# Duang60v2.net
KiCad netlist of a schematic drawn in Altium Designer
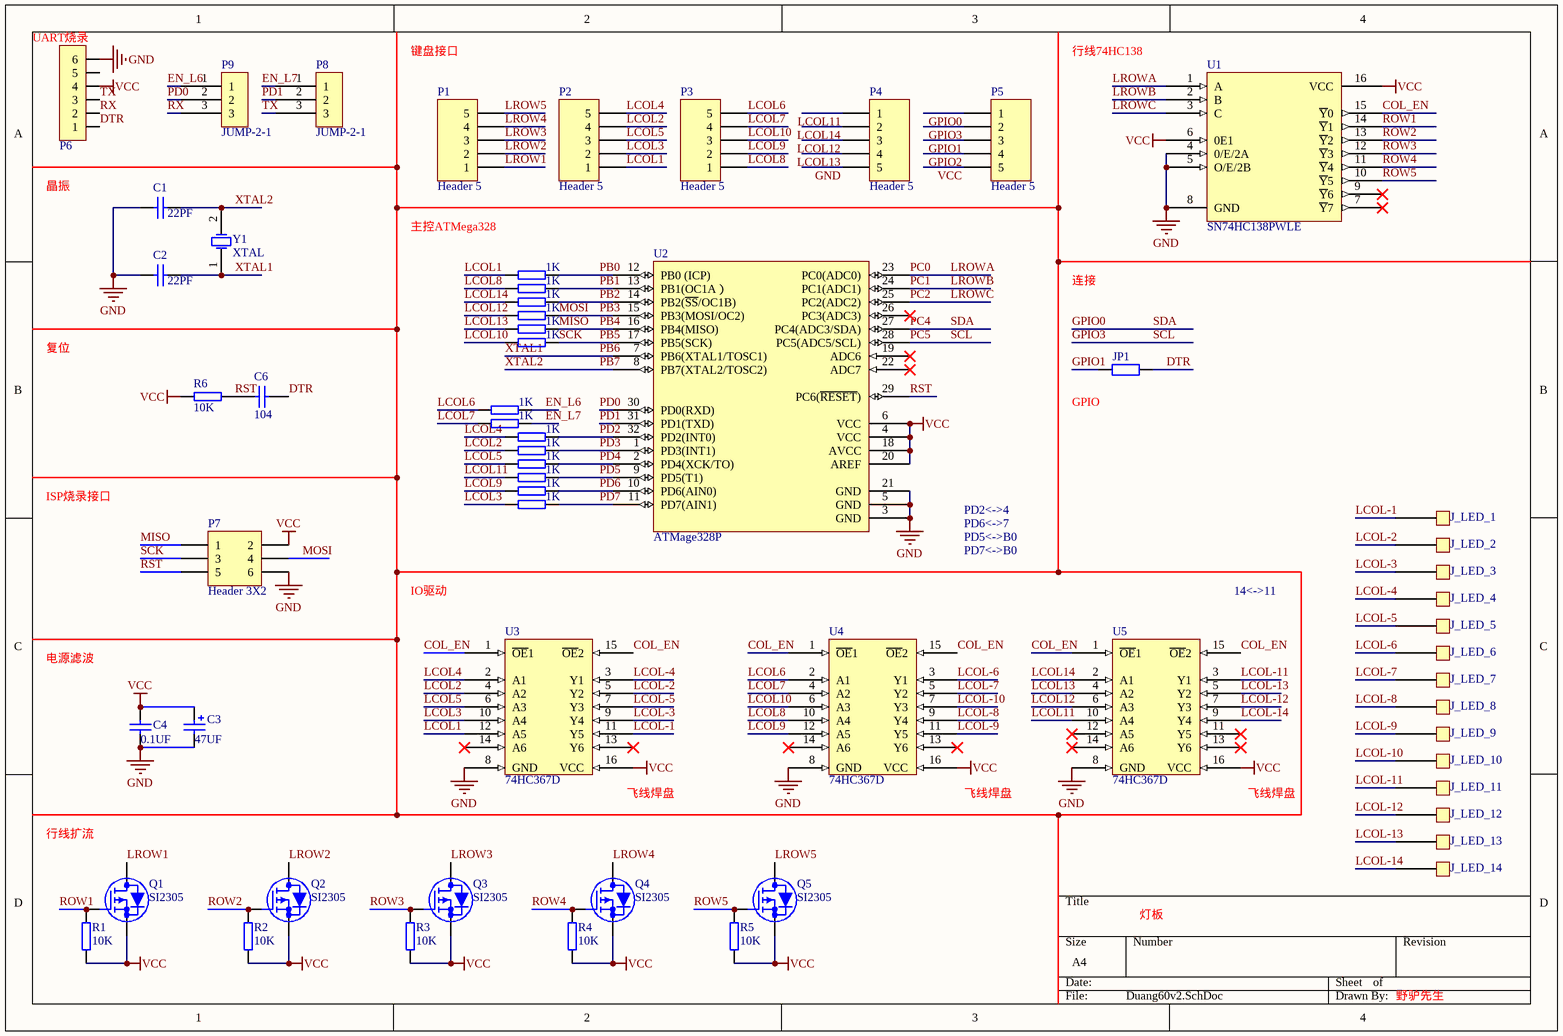
[diagram p0: Duang60v2.SchDoc]

(export (version "E")
  (design (tool "Eeschema 10.0.6"))
  (components
    (comp (ref "C1")
      (value "22PF")
      (footprint "c0805")
      (description "Capacitor (Semiconductor SIM Model)")
      (fields (field (name "Comment") "Cap Semi") (field (name "PUBLISHER") "Altium Limited"))
      (libsource (lib "Miscellaneous Devices") (part "Cap Semi"))
    )
    (comp (ref "C2")
      (value "22PF")
      (footprint "c0805")
      (description "Capacitor (Semiconductor SIM Model)")
      (fields (field (name "Comment") "Cap Semi") (field (name "PUBLISHER") "Altium Limited"))
      (libsource (lib "Miscellaneous Devices") (part "Cap Semi"))
    )
    (comp (ref "C3")
      (value "47UF")
      (footprint "CAPT3216")
      (description "Polarized Capacitor (Axial)")
      (fields (field (name "Comment") "Cap Pol2") (field (name "PUBLISHER") "Altium Limited"))
      (libsource (lib "Miscellaneous Devices") (part "Cap Pol2"))
    )
    (comp (ref "C4")
      (value "0.1UF")
      (footprint "c0805")
      (description "Capacitor (Semiconductor SIM Model)")
      (fields (field (name "Comment") "Cap Semi") (field (name "PUBLISHER") "Altium Limited"))
      (libsource (lib "Miscellaneous Devices") (part "Cap Semi"))
    )
    (comp (ref "C6")
      (value "104")
      (footprint "c0805")
      (description "Chip Capacitor, Silkscreen Border")
      (fields
        (field (name "VOLTAGE") "63V")
        (field (name "TOLERANCE") "Y5V")
        (field (name "PUBLISHER") "Altium Limited")
      )
      (libsource (lib "Miscellaneous Integrated Library") (part "Cap Chip 2"))
    )
    (comp (ref "JP1")
      (value "0")
      (footprint "c0805")
      (description "Resistor")
      (libsource (lib "SCH_Passive") (part "Res_0805"))
    )
    (comp (ref "J_LED_1") (value "JUMP1") (footprint "焊盘") (libsource (lib "SCH_Other") (part "JUMP1")))
    (comp (ref "J_LED_2") (value "JUMP1") (footprint "焊盘") (libsource (lib "SCH_Other") (part "JUMP1")))
    (comp (ref "J_LED_3") (value "JUMP1") (footprint "焊盘") (libsource (lib "SCH_Other") (part "JUMP1")))
    (comp (ref "J_LED_4") (value "JUMP1") (footprint "焊盘") (libsource (lib "SCH_Other") (part "JUMP1")))
    (comp (ref "J_LED_5") (value "JUMP1") (footprint "焊盘") (libsource (lib "SCH_Other") (part "JUMP1")))
    (comp (ref "J_LED_6") (value "JUMP1") (footprint "焊盘") (libsource (lib "SCH_Other") (part "JUMP1")))
    (comp (ref "J_LED_7") (value "JUMP1") (footprint "焊盘") (libsource (lib "SCH_Other") (part "JUMP1")))
    (comp (ref "J_LED_8") (value "JUMP1") (footprint "焊盘") (libsource (lib "SCH_Other") (part "JUMP1")))
    (comp (ref "J_LED_9") (value "JUMP1") (footprint "焊盘") (libsource (lib "SCH_Other") (part "JUMP1")))
    (comp (ref "J_LED_10") (value "JUMP1") (footprint "焊盘") (libsource (lib "SCH_Other") (part "JUMP1")))
    (comp (ref "J_LED_11") (value "JUMP1") (footprint "焊盘") (libsource (lib "SCH_Other") (part "JUMP1")))
    (comp (ref "J_LED_12") (value "JUMP1") (footprint "焊盘") (libsource (lib "SCH_Other") (part "JUMP1")))
    (comp (ref "J_LED_13") (value "JUMP1") (footprint "焊盘") (libsource (lib "SCH_Other") (part "JUMP1")))
    (comp (ref "J_LED_14") (value "JUMP1") (footprint "焊盘") (libsource (lib "SCH_Other") (part "JUMP1")))
    (comp (ref "P1")
      (value "Header 5")
      (footprint "HDR1X5")
      (description "Header, 5-Pin")
      (fields (field (name "PUBLISHER") "Altium Limited"))
      (libsource (lib "Miscellaneous Connectors") (part "Header 5"))
    )
    (comp (ref "P2")
      (value "Header 5")
      (footprint "HDR1X5")
      (description "Header, 5-Pin")
      (fields (field (name "PUBLISHER") "Altium Limited"))
      (libsource (lib "Miscellaneous Connectors") (part "Header 5"))
    )
    (comp (ref "P3")
      (value "Header 5")
      (footprint "HDR1X5")
      (description "Header, 5-Pin")
      (fields (field (name "PUBLISHER") "Altium Limited"))
      (libsource (lib "Miscellaneous Connectors") (part "Header 5"))
    )
    (comp (ref "P4")
      (value "Header 5")
      (footprint "HDR1X5")
      (description "Header, 5-Pin")
      (fields (field (name "PUBLISHER") "Altium Limited"))
      (libsource (lib "") (part "Header 5_1"))
    )
    (comp (ref "P5")
      (value "Header 5")
      (footprint "HDR1X5")
      (description "Header, 5-Pin")
      (fields (field (name "PUBLISHER") "Altium Limited"))
      (libsource (lib "") (part "Header 5_1"))
    )
    (comp (ref "P6")
      (value "HDR1X6_180_2.54")
      (footprint "PCB_Connector:HDR1X6_180_2.54")
      (description "Header")
      (libsource (lib "SCH_Connector") (part "HDR1X6_180_2.54"))
    )
    (comp (ref "P7")
      (value "Header 3X2")
      (footprint "HDR2X3")
      (description "Header, 3-Pin, Dual row")
      (fields (field (name "PUBLISHER") "Altium Limited"))
      (libsource (lib "Miscellaneous Connectors") (part "Header 3X2"))
    )
    (comp (ref "P8")
      (value "JUMP-2-1")
      (footprint "JUMP-2-1")
      (libsource (lib "SCH_Other") (part "JUMP-2-1"))
    )
    (comp (ref "P9")
      (value "JUMP-2-1")
      (footprint "JUMP-2-1")
      (libsource (lib "SCH_Other") (part "JUMP-2-1"))
    )
    (comp (ref "Q1")
      (value "SI2305")
      (footprint "si2312")
      (description "P-Channel MOSFET")
      (fields (field (name "PARTNUMBER") "SI2305") (field (name "PUBLISHER") "Altium Limited"))
      (libsource (lib "Miscellaneous Integrated Library") (part "MOSFET-P"))
    )
    (comp (ref "Q2")
      (value "SI2305")
      (footprint "si2312")
      (description "P-Channel MOSFET")
      (fields (field (name "PARTNUMBER") "SI2305") (field (name "PUBLISHER") "Altium Limited"))
      (libsource (lib "Miscellaneous Integrated Library") (part "MOSFET-P"))
    )
    (comp (ref "Q3")
      (value "SI2305")
      (footprint "si2312")
      (description "P-Channel MOSFET")
      (fields (field (name "PARTNUMBER") "SI2305") (field (name "PUBLISHER") "Altium Limited"))
      (libsource (lib "Miscellaneous Integrated Library") (part "MOSFET-P"))
    )
    (comp (ref "Q4")
      (value "SI2305")
      (footprint "si2312")
      (description "P-Channel MOSFET")
      (fields (field (name "PARTNUMBER") "SI2305") (field (name "PUBLISHER") "Altium Limited"))
      (libsource (lib "Miscellaneous Integrated Library") (part "MOSFET-P"))
    )
    (comp (ref "Q5")
      (value "SI2305")
      (footprint "si2312")
      (description "P-Channel MOSFET")
      (fields (field (name "PARTNUMBER") "SI2305") (field (name "PUBLISHER") "Altium Limited"))
      (libsource (lib "Miscellaneous Integrated Library") (part "MOSFET-P"))
    )
    (comp (ref "R1")
      (value "10K")
      (footprint "r0806")
      (description "Chip Resistor, Border Silkscreen On PCB Library")
      (fields (field (name "TOLERANCE") "5%") (field (name "PUBLISHER") "Altium Limited"))
      (libsource (lib "Miscellaneous Integrated Library") (part "Res Chip 2p 2"))
    )
    (comp (ref "R2")
      (value "10K")
      (footprint "r0806")
      (description "Chip Resistor, Border Silkscreen On PCB Library")
      (fields (field (name "TOLERANCE") "5%") (field (name "PUBLISHER") "Altium Limited"))
      (libsource (lib "Miscellaneous Integrated Library") (part "Res Chip 2p 2"))
    )
    (comp (ref "R3")
      (value "10K")
      (footprint "r0806")
      (description "Chip Resistor, Border Silkscreen On PCB Library")
      (fields (field (name "TOLERANCE") "5%") (field (name "PUBLISHER") "Altium Limited"))
      (libsource (lib "Miscellaneous Integrated Library") (part "Res Chip 2p 2"))
    )
    (comp (ref "R4")
      (value "10K")
      (footprint "r0806")
      (description "Chip Resistor, Border Silkscreen On PCB Library")
      (fields (field (name "TOLERANCE") "5%") (field (name "PUBLISHER") "Altium Limited"))
      (libsource (lib "Miscellaneous Integrated Library") (part "Res Chip 2p 2"))
    )
    (comp (ref "R5")
      (value "10K")
      (footprint "r0806")
      (description "Chip Resistor, Border Silkscreen On PCB Library")
      (fields (field (name "TOLERANCE") "5%") (field (name "PUBLISHER") "Altium Limited"))
      (libsource (lib "Miscellaneous Integrated Library") (part "Res Chip 2p 2"))
    )
    (comp (ref "R6")
      (value "10K")
      (footprint "r0806")
      (description "Chip Resistor, Border Silkscreen On PCB Library")
      (fields (field (name "TOLERANCE") "5%") (field (name "PUBLISHER") "Altium Limited"))
      (libsource (lib "Miscellaneous Integrated Library") (part "Res Chip 2p 2"))
    )
    (comp (ref "R7")
      (value "1K")
      (footprint "JP")
      (description "Chip Resistor, Border Silkscreen On PCB Library")
      (fields
        (field (name "TOLERANCE") "5%")
        (field (name "Comment") "1k")
        (field (name "PUBLISHER") "Altium Limited")
      )
      (libsource (lib "Miscellaneous Integrated Library") (part "Res Chip 2p 2"))
    )
    (comp (ref "R8")
      (value "1K")
      (footprint "JP")
      (description "Chip Resistor, Border Silkscreen On PCB Library")
      (fields
        (field (name "TOLERANCE") "5%")
        (field (name "Comment") "1k")
        (field (name "PUBLISHER") "Altium Limited")
      )
      (libsource (lib "Miscellaneous Integrated Library") (part "Res Chip 2p 2"))
    )
    (comp (ref "R9")
      (value "1K")
      (footprint "JP")
      (description "Chip Resistor, Border Silkscreen On PCB Library")
      (fields
        (field (name "TOLERANCE") "5%")
        (field (name "Comment") "1k")
        (field (name "PUBLISHER") "Altium Limited")
      )
      (libsource (lib "Miscellaneous Integrated Library") (part "Res Chip 2p 2"))
    )
    (comp (ref "R10")
      (value "1K")
      (footprint "JP")
      (description "Chip Resistor, Border Silkscreen On PCB Library")
      (fields
        (field (name "TOLERANCE") "5%")
        (field (name "Comment") "1k")
        (field (name "PUBLISHER") "Altium Limited")
      )
      (libsource (lib "Miscellaneous Integrated Library") (part "Res Chip 2p 2"))
    )
    (comp (ref "R11")
      (value "1K")
      (footprint "JP")
      (description "Chip Resistor, Border Silkscreen On PCB Library")
      (fields
        (field (name "TOLERANCE") "5%")
        (field (name "Comment") "1k")
        (field (name "PUBLISHER") "Altium Limited")
      )
      (libsource (lib "Miscellaneous Integrated Library") (part "Res Chip 2p 2"))
    )
    (comp (ref "R12")
      (value "1K")
      (footprint "JP")
      (description "Chip Resistor, Border Silkscreen On PCB Library")
      (fields
        (field (name "TOLERANCE") "5%")
        (field (name "Comment") "1k")
        (field (name "PUBLISHER") "Altium Limited")
      )
      (libsource (lib "Miscellaneous Integrated Library") (part "Res Chip 2p 2"))
    )
    (comp (ref "R13")
      (value "1K")
      (footprint "JP")
      (description "Chip Resistor, Border Silkscreen On PCB Library")
      (fields
        (field (name "TOLERANCE") "5%")
        (field (name "Comment") "1k")
        (field (name "PUBLISHER") "Altium Limited")
      )
      (libsource (lib "Miscellaneous Integrated Library") (part "Res Chip 2p 2"))
    )
    (comp (ref "R14")
      (value "1K")
      (footprint "JP")
      (description "Chip Resistor, Border Silkscreen On PCB Library")
      (fields
        (field (name "TOLERANCE") "5%")
        (field (name "Comment") "1k")
        (field (name "PUBLISHER") "Altium Limited")
      )
      (libsource (lib "Miscellaneous Integrated Library") (part "Res Chip 2p 2"))
    )
    (comp (ref "R15")
      (value "1K")
      (footprint "JP")
      (description "Chip Resistor, Border Silkscreen On PCB Library")
      (fields
        (field (name "TOLERANCE") "5%")
        (field (name "Comment") "1k")
        (field (name "PUBLISHER") "Altium Limited")
      )
      (libsource (lib "Miscellaneous Integrated Library") (part "Res Chip 2p 2"))
    )
    (comp (ref "R16")
      (value "1K")
      (footprint "JP")
      (description "Chip Resistor, Border Silkscreen On PCB Library")
      (fields
        (field (name "TOLERANCE") "5%")
        (field (name "Comment") "1k")
        (field (name "PUBLISHER") "Altium Limited")
      )
      (libsource (lib "Miscellaneous Integrated Library") (part "Res Chip 2p 2"))
    )
    (comp (ref "R17")
      (value "1K")
      (footprint "JP")
      (description "Chip Resistor, Border Silkscreen On PCB Library")
      (fields
        (field (name "TOLERANCE") "5%")
        (field (name "Comment") "1k")
        (field (name "PUBLISHER") "Altium Limited")
      )
      (libsource (lib "Miscellaneous Integrated Library") (part "Res Chip 2p 2"))
    )
    (comp (ref "R18")
      (value "1K")
      (footprint "JP")
      (description "Chip Resistor, Border Silkscreen On PCB Library")
      (fields
        (field (name "TOLERANCE") "5%")
        (field (name "Comment") "1k")
        (field (name "PUBLISHER") "Altium Limited")
      )
      (libsource (lib "Miscellaneous Integrated Library") (part "Res Chip 2p 2"))
    )
    (comp (ref "R19")
      (value "1K")
      (footprint "JP")
      (description "Chip Resistor, Border Silkscreen On PCB Library")
      (fields
        (field (name "TOLERANCE") "5%")
        (field (name "Comment") "1k")
        (field (name "PUBLISHER") "Altium Limited")
      )
      (libsource (lib "Miscellaneous Integrated Library") (part "Res Chip 2p 2"))
    )
    (comp (ref "R20")
      (value "1K")
      (footprint "JP")
      (description "Chip Resistor, Border Silkscreen On PCB Library")
      (fields
        (field (name "TOLERANCE") "5%")
        (field (name "Comment") "1k")
        (field (name "PUBLISHER") "Altium Limited")
      )
      (libsource (lib "Miscellaneous Integrated Library") (part "Res Chip 2p 2"))
    )
    (comp (ref "U1")
      (value "SN74HC138PWLE")
      (footprint "TSSOP_16")
      (libsource (lib "野驴集成库") (part "SN74HC138PWLE"))
    )
    (comp (ref "U2") (value "ATMage328P") (footprint "TQFP_32") (libsource (lib "野驴集成库") (part "ATMage328P")))
    (comp (ref "U3") (value "74HC367D") (footprint "SOIC16") (libsource (lib "野驴集成库") (part "74HC367D")))
    (comp (ref "U4") (value "74HC367D") (footprint "SOIC16") (libsource (lib "野驴集成库") (part "74HC367D")))
    (comp (ref "U5") (value "74HC367D") (footprint "SOIC16") (libsource (lib "野驴集成库") (part "74HC367D")))
    (comp (ref "Y1")
      (value "XTAL")
      (footprint "XTAL_DIP")
      (description "Crystal Oscillator")
      (fields (field (name "PUBLISHER") "Altium Limited"))
      (libsource (lib "Miscellaneous Devices") (part "XTAL"))
    )
  )
  (nets
    (net (code "1") (name "/COL_EN") (class "Default")
      (node (ref "U1") (pin "15") (pinfunction "~{Y}0_15") (pintype "output"))
      (node (ref "U3") (pin "1") (pinfunction "~{OE}1_1") (pintype "input"))
      (node (ref "U3") (pin "15") (pinfunction "~{OE}2_15") (pintype "input"))
      (node (ref "U4") (pin "1") (pinfunction "~{OE}1_1") (pintype "input"))
      (node (ref "U4") (pin "15") (pinfunction "~{OE}2_15") (pintype "input"))
      (node (ref "U5") (pin "1") (pinfunction "~{OE}1_1") (pintype "input"))
      (node (ref "U5") (pin "15") (pinfunction "~{OE}2_15") (pintype "input"))
    )
    (net (code "2") (name "/DTR") (class "Default")
      (node (ref "C6") (pin "2") (pinfunction "2_2") (pintype "passive"))
      (node (ref "JP1") (pin "2") (pinfunction "2_2") (pintype "passive"))
      (node (ref "P6") (pin "1") (pinfunction "1_1") (pintype "passive"))
    )
    (net (code "3") (name "/EN_L6") (class "Default")
      (node (ref "P9") (pin "1") (pinfunction "1_1") (pintype "passive"))
      (node (ref "R12") (pin "2") (pinfunction "2_2") (pintype "passive"))
    )
    (net (code "4") (name "/EN_L7") (class "Default")
      (node (ref "P8") (pin "1") (pinfunction "1_1") (pintype "passive"))
      (node (ref "R13") (pin "2") (pinfunction "2_2") (pintype "passive"))
    )
    (net (code "5") (name "/GPIO0") (class "Default")
      (node (ref "P5") (pin "1") (pinfunction "1_1") (pintype "passive"))
      (node (ref "U2") (pin "27") (pinfunction "PC4(ADC3/SDA)_27") (pintype "bidirectional"))
    )
    (net (code "6") (name "/GPIO1") (class "Default")
      (node (ref "JP1") (pin "1") (pinfunction "1_1") (pintype "passive"))
      (node (ref "P5") (pin "3") (pinfunction "3_3") (pintype "passive"))
    )
    (net (code "7") (name "/GPIO2") (class "Default")
      (node (ref "P5") (pin "4") (pinfunction "4_4") (pintype "passive"))
    )
    (net (code "8") (name "/GPIO3") (class "Default")
      (node (ref "P5") (pin "2") (pinfunction "2_2") (pintype "passive"))
      (node (ref "U2") (pin "28") (pinfunction "PC5(ADC5/SCL)_28") (pintype "bidirectional"))
    )
    (net (code "9") (name "/LCOL-1") (class "Default")
      (node (ref "J_LED_1") (pin "1") (pinfunction "1_1") (pintype "passive"))
      (node (ref "U3") (pin "11") (pinfunction "Y5_11") (pintype "input"))
    )
    (net (code "10") (name "/LCOL-2") (class "Default")
      (node (ref "J_LED_2") (pin "1") (pinfunction "1_1") (pintype "passive"))
      (node (ref "U3") (pin "5") (pinfunction "Y2_5") (pintype "input"))
    )
    (net (code "11") (name "/LCOL-3") (class "Default")
      (node (ref "J_LED_3") (pin "1") (pinfunction "1_1") (pintype "passive"))
      (node (ref "U3") (pin "9") (pinfunction "Y4_9") (pintype "input"))
    )
    (net (code "12") (name "/LCOL-4") (class "Default")
      (node (ref "J_LED_4") (pin "1") (pinfunction "1_1") (pintype "passive"))
      (node (ref "U3") (pin "3") (pinfunction "Y1_3") (pintype "input"))
    )
    (net (code "13") (name "/LCOL-5") (class "Default")
      (node (ref "J_LED_5") (pin "1") (pinfunction "1_1") (pintype "passive"))
      (node (ref "U3") (pin "7") (pinfunction "Y3_7") (pintype "input"))
    )
    (net (code "14") (name "/LCOL-6") (class "Default")
      (node (ref "J_LED_6") (pin "1") (pinfunction "1_1") (pintype "passive"))
      (node (ref "U4") (pin "3") (pinfunction "Y1_3") (pintype "input"))
    )
    (net (code "15") (name "/LCOL-7") (class "Default")
      (node (ref "J_LED_7") (pin "1") (pinfunction "1_1") (pintype "passive"))
      (node (ref "U4") (pin "5") (pinfunction "Y2_5") (pintype "input"))
    )
    (net (code "16") (name "/LCOL-8") (class "Default")
      (node (ref "J_LED_8") (pin "1") (pinfunction "1_1") (pintype "passive"))
      (node (ref "U4") (pin "9") (pinfunction "Y4_9") (pintype "input"))
    )
    (net (code "17") (name "/LCOL-9") (class "Default")
      (node (ref "J_LED_9") (pin "1") (pinfunction "1_1") (pintype "passive"))
      (node (ref "U4") (pin "11") (pinfunction "Y5_11") (pintype "input"))
    )
    (net (code "18") (name "/LCOL-10") (class "Default")
      (node (ref "J_LED_10") (pin "1") (pinfunction "1_1") (pintype "passive"))
      (node (ref "U4") (pin "7") (pinfunction "Y3_7") (pintype "input"))
    )
    (net (code "19") (name "/LCOL-11") (class "Default")
      (node (ref "J_LED_11") (pin "1") (pinfunction "1_1") (pintype "passive"))
      (node (ref "U5") (pin "3") (pinfunction "Y1_3") (pintype "input"))
    )
    (net (code "20") (name "/LCOL-12") (class "Default")
      (node (ref "J_LED_12") (pin "1") (pinfunction "1_1") (pintype "passive"))
      (node (ref "U5") (pin "7") (pinfunction "Y3_7") (pintype "input"))
    )
    (net (code "21") (name "/LCOL-13") (class "Default")
      (node (ref "J_LED_13") (pin "1") (pinfunction "1_1") (pintype "passive"))
      (node (ref "U5") (pin "5") (pinfunction "Y2_5") (pintype "input"))
    )
    (net (code "22") (name "/LCOL-14") (class "Default")
      (node (ref "J_LED_14") (pin "1") (pinfunction "1_1") (pintype "passive"))
      (node (ref "U5") (pin "9") (pinfunction "Y4_9") (pintype "input"))
    )
    (net (code "23") (name "/LCOL1") (class "Default")
      (node (ref "P2") (pin "1") (pinfunction "1_1") (pintype "passive"))
      (node (ref "R9") (pin "1") (pinfunction "1_1") (pintype "passive"))
      (node (ref "U3") (pin "12") (pinfunction "A5_12") (pintype "input"))
    )
    (net (code "24") (name "/LCOL2") (class "Default")
      (node (ref "P2") (pin "4") (pinfunction "4_4") (pintype "passive"))
      (node (ref "R8") (pin "1") (pinfunction "1_1") (pintype "passive"))
      (node (ref "U3") (pin "4") (pinfunction "A2_4") (pintype "input"))
    )
    (net (code "25") (name "/LCOL3") (class "Default")
      (node (ref "P2") (pin "2") (pinfunction "2_2") (pintype "passive"))
      (node (ref "R7") (pin "1") (pinfunction "1_1") (pintype "passive"))
      (node (ref "U3") (pin "10") (pinfunction "A4_10") (pintype "input"))
    )
    (net (code "26") (name "/LCOL4") (class "Default")
      (node (ref "P2") (pin "5") (pinfunction "5_5") (pintype "passive"))
      (node (ref "R10") (pin "1") (pinfunction "1_1") (pintype "passive"))
      (node (ref "U3") (pin "2") (pinfunction "A1_2") (pintype "input"))
    )
    (net (code "27") (name "/LCOL5") (class "Default")
      (node (ref "P2") (pin "3") (pinfunction "3_3") (pintype "passive"))
      (node (ref "R11") (pin "1") (pinfunction "1_1") (pintype "passive"))
      (node (ref "U3") (pin "6") (pinfunction "A3_6") (pintype "input"))
    )
    (net (code "28") (name "/LCOL6") (class "Default")
      (node (ref "P3") (pin "5") (pinfunction "5_5") (pintype "passive"))
      (node (ref "R12") (pin "1") (pinfunction "1_1") (pintype "passive"))
      (node (ref "U4") (pin "2") (pinfunction "A1_2") (pintype "input"))
    )
    (net (code "29") (name "/LCOL7") (class "Default")
      (node (ref "P3") (pin "4") (pinfunction "4_4") (pintype "passive"))
      (node (ref "R13") (pin "1") (pinfunction "1_1") (pintype "passive"))
      (node (ref "U4") (pin "4") (pinfunction "A2_4") (pintype "input"))
    )
    (net (code "30") (name "/LCOL8") (class "Default")
      (node (ref "P3") (pin "1") (pinfunction "1_1") (pintype "passive"))
      (node (ref "R14") (pin "1") (pinfunction "1_1") (pintype "passive"))
      (node (ref "U4") (pin "10") (pinfunction "A4_10") (pintype "input"))
    )
    (net (code "31") (name "/LCOL9") (class "Default")
      (node (ref "P3") (pin "2") (pinfunction "2_2") (pintype "passive"))
      (node (ref "R15") (pin "1") (pinfunction "1_1") (pintype "passive"))
      (node (ref "U4") (pin "12") (pinfunction "A5_12") (pintype "input"))
    )
    (net (code "32") (name "/LCOL10") (class "Default")
      (node (ref "P3") (pin "3") (pinfunction "3_3") (pintype "passive"))
      (node (ref "R16") (pin "1") (pinfunction "1_1") (pintype "passive"))
      (node (ref "U4") (pin "6") (pinfunction "A3_6") (pintype "input"))
    )
    (net (code "33") (name "/LCOL11") (class "Default")
      (node (ref "P4") (pin "1") (pinfunction "1_1") (pintype "passive"))
      (node (ref "R20") (pin "1") (pinfunction "1_1") (pintype "passive"))
      (node (ref "U5") (pin "10") (pinfunction "A4_10") (pintype "input"))
    )
    (net (code "34") (name "/LCOL12") (class "Default")
      (node (ref "P4") (pin "3") (pinfunction "3_3") (pintype "passive"))
      (node (ref "R18") (pin "1") (pinfunction "1_1") (pintype "passive"))
      (node (ref "U5") (pin "6") (pinfunction "A3_6") (pintype "input"))
    )
    (net (code "35") (name "/LCOL13") (class "Default")
      (node (ref "P4") (pin "4") (pinfunction "4_4") (pintype "passive"))
      (node (ref "R19") (pin "1") (pinfunction "1_1") (pintype "passive"))
      (node (ref "U5") (pin "4") (pinfunction "A2_4") (pintype "input"))
    )
    (net (code "36") (name "/LCOL14") (class "Default")
      (node (ref "P4") (pin "2") (pinfunction "2_2") (pintype "passive"))
      (node (ref "R17") (pin "1") (pinfunction "1_1") (pintype "passive"))
      (node (ref "U5") (pin "2") (pinfunction "A1_2") (pintype "input"))
    )
    (net (code "37") (name "/LROW1") (class "Default")
      (node (ref "P1") (pin "1") (pinfunction "1_1") (pintype "passive"))
      (node (ref "Q1") (pin "2") (pinfunction "D_2") (pintype "passive"))
    )
    (net (code "38") (name "/LROW2") (class "Default")
      (node (ref "P1") (pin "2") (pinfunction "2_2") (pintype "passive"))
      (node (ref "Q2") (pin "2") (pinfunction "D_2") (pintype "passive"))
    )
    (net (code "39") (name "/LROW3") (class "Default")
      (node (ref "P1") (pin "3") (pinfunction "3_3") (pintype "passive"))
      (node (ref "Q3") (pin "2") (pinfunction "D_2") (pintype "passive"))
    )
    (net (code "40") (name "/LROW4") (class "Default")
      (node (ref "P1") (pin "4") (pinfunction "4_4") (pintype "passive"))
      (node (ref "Q4") (pin "2") (pinfunction "D_2") (pintype "passive"))
    )
    (net (code "41") (name "/LROW5") (class "Default")
      (node (ref "P1") (pin "5") (pinfunction "5_5") (pintype "passive"))
      (node (ref "Q5") (pin "2") (pinfunction "D_2") (pintype "passive"))
    )
    (net (code "42") (name "/LROWA") (class "Default")
      (node (ref "U1") (pin "1") (pinfunction "A_1") (pintype "input"))
      (node (ref "U2") (pin "23") (pinfunction "PC0(ADC0)_23") (pintype "bidirectional"))
    )
    (net (code "43") (name "/LROWB") (class "Default")
      (node (ref "U1") (pin "2") (pinfunction "B_2") (pintype "input"))
      (node (ref "U2") (pin "24") (pinfunction "PC1(ADC1)_24") (pintype "bidirectional"))
    )
    (net (code "44") (name "/LROWC") (class "Default")
      (node (ref "U1") (pin "3") (pinfunction "C_3") (pintype "input"))
      (node (ref "U2") (pin "25") (pinfunction "PC2(ADC2)_25") (pintype "bidirectional"))
    )
    (net (code "45") (name "/MISO") (class "Default")
      (node (ref "P7") (pin "1") (pinfunction "1_1") (pintype "passive"))
      (node (ref "R19") (pin "2") (pinfunction "2_2") (pintype "passive"))
      (node (ref "U2") (pin "16") (pinfunction "PB4(MISO)_16") (pintype "bidirectional"))
    )
    (net (code "46") (name "/MOSI") (class "Default")
      (node (ref "P7") (pin "4") (pinfunction "4_4") (pintype "passive"))
      (node (ref "R18") (pin "2") (pinfunction "2_2") (pintype "passive"))
      (node (ref "U2") (pin "15") (pinfunction "PB3(MOSI/OC2)_15") (pintype "bidirectional"))
    )
    (net (code "47") (name "/PB0") (class "Default")
      (node (ref "R9") (pin "2") (pinfunction "2_2") (pintype "passive"))
      (node (ref "U2") (pin "12") (pinfunction "PB0_(ICP)_12") (pintype "bidirectional"))
    )
    (net (code "48") (name "/PB1") (class "Default")
      (node (ref "R14") (pin "2") (pinfunction "2_2") (pintype "passive"))
      (node (ref "U2") (pin "13") (pinfunction "PB1(OC1A）_13") (pintype "bidirectional"))
    )
    (net (code "49") (name "/PB2") (class "Default")
      (node (ref "R17") (pin "2") (pinfunction "2_2") (pintype "passive"))
      (node (ref "U2") (pin "14") (pinfunction "PB2(~{SS}/OC1B)_14") (pintype "bidirectional"))
    )
    (net (code "50") (name "/PB5") (class "Default")
      (node (ref "P7") (pin "3") (pinfunction "3_3") (pintype "passive"))
      (node (ref "R16") (pin "2") (pinfunction "2_2") (pintype "passive"))
      (node (ref "U2") (pin "17") (pinfunction "PB5(SCK)_17") (pintype "bidirectional"))
    )
    (net (code "51") (name "/PB6") (class "Default")
      (node (ref "C2") (pin "1") (pinfunction "1_1") (pintype "passive"))
      (node (ref "U2") (pin "7") (pinfunction "PB6(XTAL1/TOSC1)_7") (pintype "bidirectional"))
      (node (ref "Y1") (pin "1") (pinfunction "OSC1_1") (pintype "passive"))
    )
    (net (code "52") (name "/PB7") (class "Default")
      (node (ref "C1") (pin "1") (pinfunction "1_1") (pintype "passive"))
      (node (ref "U2") (pin "8") (pinfunction "PB7(XTAL2/TOSC2)_8") (pintype "bidirectional"))
      (node (ref "Y1") (pin "2") (pinfunction "OSC2_2") (pintype "passive"))
    )
    (net (code "53") (name "/PD0") (class "Default")
      (node (ref "P9") (pin "2") (pinfunction "2_2") (pintype "passive"))
      (node (ref "U2") (pin "30") (pinfunction "PD0(RXD)_30") (pintype "bidirectional"))
    )
    (net (code "54") (name "/PD1") (class "Default")
      (node (ref "P8") (pin "2") (pinfunction "2_2") (pintype "passive"))
      (node (ref "U2") (pin "31") (pinfunction "PD1(TXD)_31") (pintype "bidirectional"))
    )
    (net (code "55") (name "/PD2") (class "Default")
      (node (ref "R10") (pin "2") (pinfunction "2_2") (pintype "passive"))
      (node (ref "U2") (pin "32") (pinfunction "PD2(INT0)_32") (pintype "bidirectional"))
    )
    (net (code "56") (name "/PD3") (class "Default")
      (node (ref "R8") (pin "2") (pinfunction "2_2") (pintype "passive"))
      (node (ref "U2") (pin "1") (pinfunction "PD3(INT1)_1") (pintype "bidirectional"))
    )
    (net (code "57") (name "/PD4") (class "Default")
      (node (ref "R11") (pin "2") (pinfunction "2_2") (pintype "passive"))
      (node (ref "U2") (pin "2") (pinfunction "PD4(XCK/TO)_2") (pintype "bidirectional"))
    )
    (net (code "58") (name "/PD5") (class "Default")
      (node (ref "R20") (pin "2") (pinfunction "2_2") (pintype "passive"))
      (node (ref "U2") (pin "9") (pinfunction "PD5(T1)_9") (pintype "bidirectional"))
    )
    (net (code "59") (name "/PD6") (class "Default")
      (node (ref "R15") (pin "2") (pinfunction "2_2") (pintype "passive"))
      (node (ref "U2") (pin "10") (pinfunction "PD6(AIN0)_10") (pintype "bidirectional"))
    )
    (net (code "60") (name "/PD7") (class "Default")
      (node (ref "R7") (pin "2") (pinfunction "2_2") (pintype "passive"))
      (node (ref "U2") (pin "11") (pinfunction "PD7(AIN1)_11") (pintype "bidirectional"))
    )
    (net (code "61") (name "/ROW1") (class "Default")
      (node (ref "Q1") (pin "1") (pinfunction "G_1") (pintype "passive"))
      (node (ref "R1") (pin "2") (pinfunction "2_2") (pintype "passive"))
      (node (ref "U1") (pin "14") (pinfunction "~{Y}1_14") (pintype "output"))
    )
    (net (code "62") (name "/ROW2") (class "Default")
      (node (ref "Q2") (pin "1") (pinfunction "G_1") (pintype "passive"))
      (node (ref "R2") (pin "2") (pinfunction "2_2") (pintype "passive"))
      (node (ref "U1") (pin "13") (pinfunction "~{Y}2_13") (pintype "output"))
    )
    (net (code "63") (name "/ROW3") (class "Default")
      (node (ref "Q3") (pin "1") (pinfunction "G_1") (pintype "passive"))
      (node (ref "R3") (pin "2") (pinfunction "2_2") (pintype "passive"))
      (node (ref "U1") (pin "12") (pinfunction "~{Y}3_12") (pintype "output"))
    )
    (net (code "64") (name "/ROW4") (class "Default")
      (node (ref "Q4") (pin "1") (pinfunction "G_1") (pintype "passive"))
      (node (ref "R4") (pin "2") (pinfunction "2_2") (pintype "passive"))
      (node (ref "U1") (pin "11") (pinfunction "~{Y}4_11") (pintype "output"))
    )
    (net (code "65") (name "/ROW5") (class "Default")
      (node (ref "Q5") (pin "1") (pinfunction "G_1") (pintype "passive"))
      (node (ref "R5") (pin "2") (pinfunction "2_2") (pintype "passive"))
      (node (ref "U1") (pin "10") (pinfunction "~{Y}5_10") (pintype "output"))
    )
    (net (code "66") (name "/RST") (class "Default")
      (node (ref "C6") (pin "1") (pinfunction "1_1") (pintype "passive"))
      (node (ref "P7") (pin "5") (pinfunction "5_5") (pintype "passive"))
      (node (ref "R6") (pin "1") (pinfunction "1_1") (pintype "passive"))
      (node (ref "U2") (pin "29") (pinfunction "PC6(~{RESET})_29") (pintype "bidirectional"))
    )
    (net (code "67") (name "/RX") (class "Default")
      (node (ref "P6") (pin "2") (pinfunction "2_2") (pintype "passive"))
      (node (ref "P9") (pin "3") (pinfunction "3_3") (pintype "passive"))
    )
    (net (code "68") (name "/TX") (class "Default")
      (node (ref "P6") (pin "3") (pinfunction "3_3") (pintype "passive"))
      (node (ref "P8") (pin "3") (pinfunction "3_3") (pintype "passive"))
    )
    (net (code "69") (name "GND") (class "Default")
      (node (ref "C1") (pin "2") (pinfunction "2_2") (pintype "passive"))
      (node (ref "C2") (pin "2") (pinfunction "2_2") (pintype "passive"))
      (node (ref "C3") (pin "2") (pinfunction "2_2") (pintype "passive"))
      (node (ref "C4") (pin "1") (pinfunction "1_1") (pintype "passive"))
      (node (ref "P4") (pin "5") (pinfunction "5_5") (pintype "passive"))
      (node (ref "P6") (pin "6") (pinfunction "6_6") (pintype "passive"))
      (node (ref "P7") (pin "6") (pinfunction "6_6") (pintype "passive"))
      (node (ref "U1") (pin "4") (pinfunction "0/E/2A_4") (pintype "input"))
      (node (ref "U1") (pin "5") (pinfunction "O/E/2B_5") (pintype "input"))
      (node (ref "U1") (pin "8") (pinfunction "GND_8") (pintype "passive"))
      (node (ref "U2") (pin "21") (pinfunction "GND_21") (pintype "passive"))
      (node (ref "U2") (pin "3") (pinfunction "GND_3") (pintype "passive"))
      (node (ref "U2") (pin "5") (pinfunction "GND_5") (pintype "passive"))
      (node (ref "U3") (pin "8") (pinfunction "GND_8") (pintype "input"))
      (node (ref "U4") (pin "8") (pinfunction "GND_8") (pintype "input"))
      (node (ref "U5") (pin "8") (pinfunction "GND_8") (pintype "input"))
    )
    (net (code "70") (name "VCC") (class "Default")
      (node (ref "C3") (pin "1") (pinfunction "1_1") (pintype "passive"))
      (node (ref "C4") (pin "2") (pinfunction "2_2") (pintype "passive"))
      (node (ref "P5") (pin "5") (pinfunction "5_5") (pintype "passive"))
      (node (ref "P6") (pin "4") (pinfunction "4_4") (pintype "passive"))
      (node (ref "P7") (pin "2") (pinfunction "2_2") (pintype "passive"))
      (node (ref "Q1") (pin "3") (pinfunction "S_3") (pintype "passive"))
      (node (ref "Q2") (pin "3") (pinfunction "S_3") (pintype "passive"))
      (node (ref "Q3") (pin "3") (pinfunction "S_3") (pintype "passive"))
      (node (ref "Q4") (pin "3") (pinfunction "S_3") (pintype "passive"))
      (node (ref "Q5") (pin "3") (pinfunction "S_3") (pintype "passive"))
      (node (ref "R1") (pin "1") (pinfunction "1_1") (pintype "passive"))
      (node (ref "R2") (pin "1") (pinfunction "1_1") (pintype "passive"))
      (node (ref "R3") (pin "1") (pinfunction "1_1") (pintype "passive"))
      (node (ref "R4") (pin "1") (pinfunction "1_1") (pintype "passive"))
      (node (ref "R5") (pin "1") (pinfunction "1_1") (pintype "passive"))
      (node (ref "R6") (pin "2") (pinfunction "2_2") (pintype "passive"))
      (node (ref "U1") (pin "16") (pinfunction "VCC_16") (pintype "passive"))
      (node (ref "U1") (pin "6") (pinfunction "0E1_6") (pintype "input"))
      (node (ref "U2") (pin "18") (pinfunction "AVCC_18") (pintype "passive"))
      (node (ref "U2") (pin "20") (pinfunction "AREF_20") (pintype "passive"))
      (node (ref "U2") (pin "4") (pinfunction "VCC_4") (pintype "passive"))
      (node (ref "U2") (pin "6") (pinfunction "VCC_6") (pintype "passive"))
      (node (ref "U3") (pin "16") (pinfunction "VCC_16") (pintype "input"))
      (node (ref "U4") (pin "16") (pinfunction "VCC_16") (pintype "input"))
      (node (ref "U5") (pin "16") (pinfunction "VCC_16") (pintype "input"))
    )
    (net (code "71") (name "unconnected-(P6-Pad5)") (class "Default")
      (node (ref "P6") (pin "5") (pinfunction "5_5") (pintype "passive"))
    )
    (net (code "72") (name "unconnected-(U1-~{Y}6-Pad9)") (class "Default")
      (node (ref "U1") (pin "9") (pinfunction "~{Y}6_9") (pintype "output+no_connect"))
    )
    (net (code "73") (name "unconnected-(U1-~{Y}7-Pad7)") (class "Default")
      (node (ref "U1") (pin "7") (pinfunction "~{Y}7_7") (pintype "output+no_connect"))
    )
    (net (code "74") (name "unconnected-(U2-ADC6-Pad19)") (class "Default")
      (node (ref "U2") (pin "19") (pinfunction "ADC6_19") (pintype "input+no_connect"))
    )
    (net (code "75") (name "unconnected-(U2-ADC7-Pad22)") (class "Default")
      (node (ref "U2") (pin "22") (pinfunction "ADC7_22") (pintype "input+no_connect"))
    )
    (net (code "76") (name "unconnected-(U2-PC3(ADC3)-Pad26)") (class "Default")
      (node (ref "U2") (pin "26") (pinfunction "PC3(ADC3)_26") (pintype "bidirectional+no_connect"))
    )
    (net (code "77") (name "unconnected-(U3-A6-Pad14)") (class "Default")
      (node (ref "U3") (pin "14") (pinfunction "A6_14") (pintype "input+no_connect"))
    )
    (net (code "78") (name "unconnected-(U3-Y6-Pad13)") (class "Default")
      (node (ref "U3") (pin "13") (pinfunction "Y6_13") (pintype "input+no_connect"))
    )
    (net (code "79") (name "unconnected-(U4-A6-Pad14)") (class "Default")
      (node (ref "U4") (pin "14") (pinfunction "A6_14") (pintype "input+no_connect"))
    )
    (net (code "80") (name "unconnected-(U4-Y6-Pad13)") (class "Default")
      (node (ref "U4") (pin "13") (pinfunction "Y6_13") (pintype "input+no_connect"))
    )
    (net (code "81") (name "unconnected-(U5-A5-Pad12)") (class "Default")
      (node (ref "U5") (pin "12") (pinfunction "A5_12") (pintype "input+no_connect"))
    )
    (net (code "82") (name "unconnected-(U5-A6-Pad14)") (class "Default")
      (node (ref "U5") (pin "14") (pinfunction "A6_14") (pintype "input+no_connect"))
    )
    (net (code "83") (name "unconnected-(U5-Y5-Pad11)") (class "Default")
      (node (ref "U5") (pin "11") (pinfunction "Y5_11") (pintype "input+no_connect"))
    )
    (net (code "84") (name "unconnected-(U5-Y6-Pad13)") (class "Default")
      (node (ref "U5") (pin "13") (pinfunction "Y6_13") (pintype "input+no_connect"))
    )
  )
)
